# ROS-Robot-Controller.net
KiCad netlist of a schematic drawn in Altium Designer
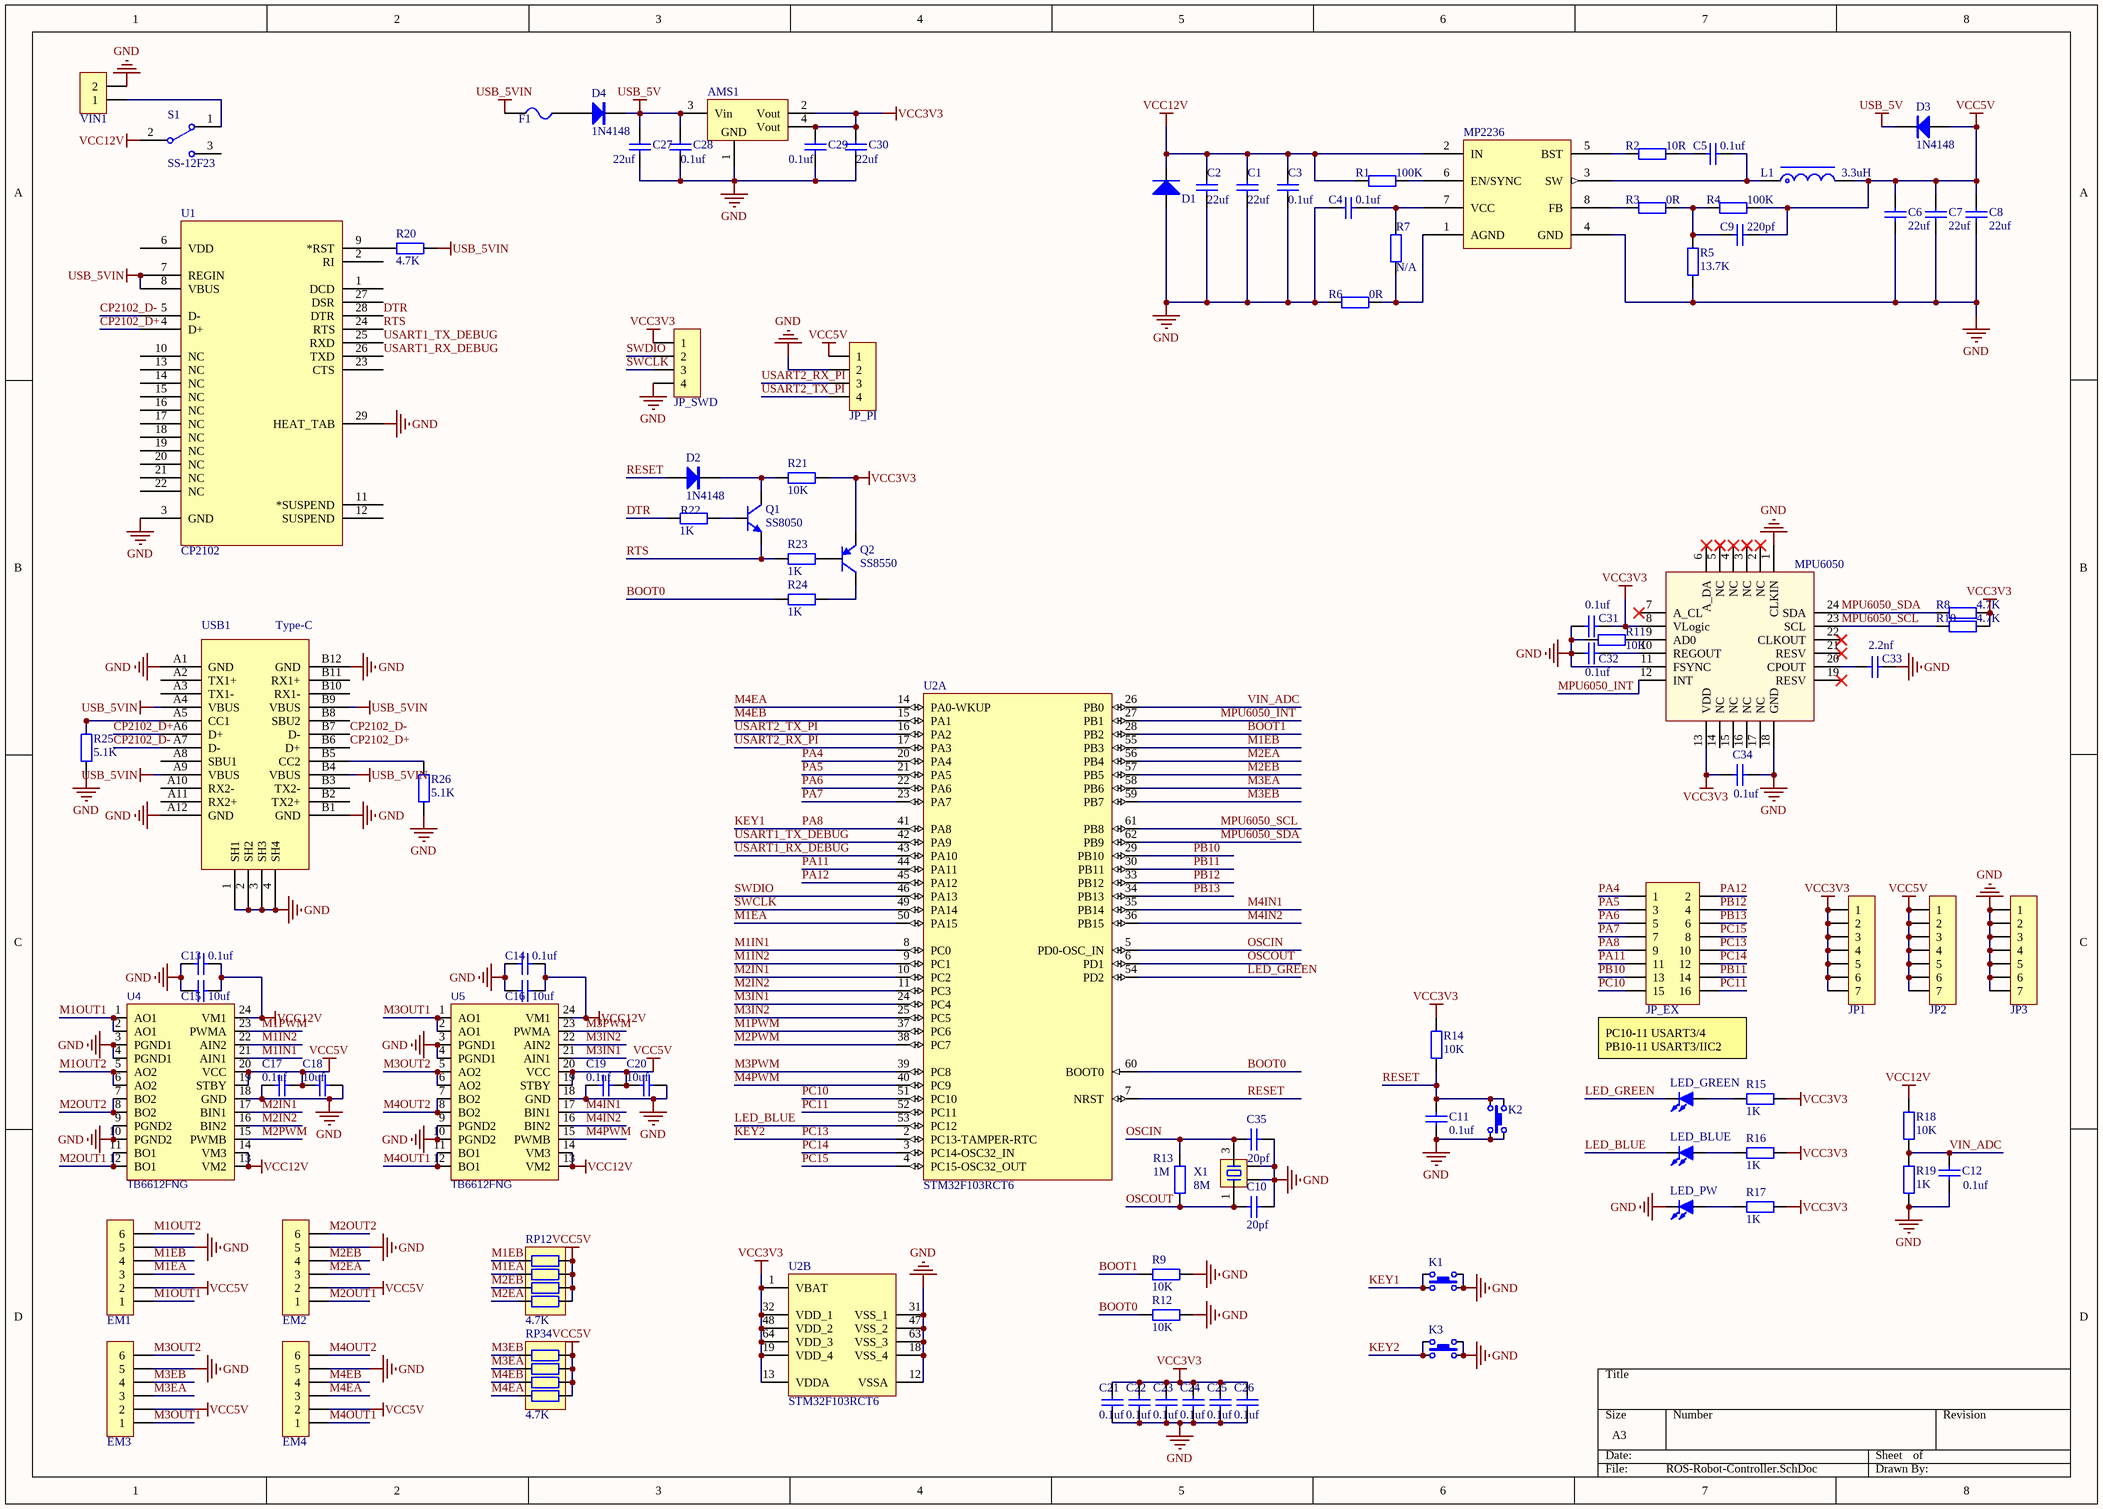
[diagram p0: ROS-Robot-Controller.SchDoc]

(export (version "E")
  (design (tool "Eeschema 10.0.6"))
  (components
    (comp (ref "AMS1")
      (value "AMS1117-3V3")
      (footprint "SOT223_L")
      (description "三端稳压芯片")
      (libsource (lib "1.1 - 电源类芯片") (part "AMS1117"))
    )
    (comp (ref "C1")
      (value "22uf")
      (footprint "C1206_L")
      (description "贴片电容")
      (libsource (lib "0.1 - 电阻-电容-电感-电位器") (part "C"))
    )
    (comp (ref "C2")
      (value "22uf")
      (footprint "C1206_L")
      (description "贴片电容")
      (libsource (lib "0.1 - 电阻-电容-电感-电位器") (part "C"))
    )
    (comp (ref "C3")
      (value "0.1uf")
      (footprint "C0603_L")
      (description "贴片电容")
      (libsource (lib "0.1 - 电阻-电容-电感-电位器") (part "C"))
    )
    (comp (ref "C4")
      (value "0.1uf")
      (footprint "C0603_L")
      (description "贴片电容")
      (libsource (lib "0.1 - 电阻-电容-电感-电位器") (part "C"))
    )
    (comp (ref "C5")
      (value "0.1uf")
      (footprint "C0603_L")
      (description "贴片电容")
      (libsource (lib "0.1 - 电阻-电容-电感-电位器") (part "C"))
    )
    (comp (ref "C6")
      (value "22uf")
      (footprint "C0805_L")
      (description "贴片电容")
      (libsource (lib "0.1 - 电阻-电容-电感-电位器") (part "C"))
    )
    (comp (ref "C7")
      (value "22uf")
      (footprint "C0805_L")
      (description "贴片电容")
      (libsource (lib "0.1 - 电阻-电容-电感-电位器") (part "C"))
    )
    (comp (ref "C8")
      (value "22uf")
      (footprint "C0805_L")
      (description "贴片电容")
      (libsource (lib "0.1 - 电阻-电容-电感-电位器") (part "C"))
    )
    (comp (ref "C9")
      (value "220pf")
      (footprint "C0603_L")
      (description "贴片电容")
      (libsource (lib "0.1 - 电阻-电容-电感-电位器") (part "C"))
    )
    (comp (ref "C10")
      (value "20pf")
      (footprint "C0402_L")
      (description "贴片电容")
      (libsource (lib "0.1 - 电阻-电容-电感-电位器") (part "C"))
    )
    (comp (ref "C11")
      (value "0.1uf")
      (footprint "C0402_L")
      (description "贴片电容")
      (libsource (lib "0.1 - 电阻-电容-电感-电位器") (part "C"))
    )
    (comp (ref "C12")
      (value "0.1uf")
      (footprint "C0603_L")
      (description "贴片电容")
      (libsource (lib "0.1 - 电阻-电容-电感-电位器") (part "C"))
    )
    (comp (ref "C13")
      (value "0.1uf")
      (footprint "C0603_L")
      (description "贴片电容")
      (libsource (lib "0.1 - 电阻-电容-电感-电位器") (part "C"))
    )
    (comp (ref "C14")
      (value "0.1uf")
      (footprint "C0603_L")
      (description "贴片电容")
      (libsource (lib "0.1 - 电阻-电容-电感-电位器") (part "C"))
    )
    (comp (ref "C15")
      (value "10uf")
      (footprint "C0603_L")
      (description "贴片电容")
      (libsource (lib "0.1 - 电阻-电容-电感-电位器") (part "C"))
    )
    (comp (ref "C16")
      (value "10uf")
      (footprint "C0603_L")
      (description "贴片电容")
      (libsource (lib "0.1 - 电阻-电容-电感-电位器") (part "C"))
    )
    (comp (ref "C17")
      (value "0.1uf")
      (footprint "C0402_L")
      (description "贴片电容")
      (libsource (lib "0.1 - 电阻-电容-电感-电位器") (part "C"))
    )
    (comp (ref "C18")
      (value "10uf")
      (footprint "C0402_L")
      (description "贴片电容")
      (libsource (lib "0.1 - 电阻-电容-电感-电位器") (part "C"))
    )
    (comp (ref "C19")
      (value "0.1uf")
      (footprint "C0402_L")
      (description "贴片电容")
      (libsource (lib "0.1 - 电阻-电容-电感-电位器") (part "C"))
    )
    (comp (ref "C20")
      (value "10uf")
      (footprint "C0402_L")
      (description "贴片电容")
      (libsource (lib "0.1 - 电阻-电容-电感-电位器") (part "C"))
    )
    (comp (ref "C21")
      (value "0.1uf")
      (footprint "C0402_L")
      (description "贴片电容")
      (libsource (lib "0.1 - 电阻-电容-电感-电位器") (part "C"))
    )
    (comp (ref "C22")
      (value "0.1uf")
      (footprint "C0402_L")
      (description "贴片电容")
      (libsource (lib "0.1 - 电阻-电容-电感-电位器") (part "C"))
    )
    (comp (ref "C23")
      (value "0.1uf")
      (footprint "C0402_L")
      (description "贴片电容")
      (libsource (lib "0.1 - 电阻-电容-电感-电位器") (part "C"))
    )
    (comp (ref "C24")
      (value "0.1uf")
      (footprint "C0402_L")
      (description "贴片电容")
      (libsource (lib "0.1 - 电阻-电容-电感-电位器") (part "C"))
    )
    (comp (ref "C25")
      (value "0.1uf")
      (footprint "C0402_L")
      (description "贴片电容")
      (libsource (lib "0.1 - 电阻-电容-电感-电位器") (part "C"))
    )
    (comp (ref "C26")
      (value "0.1uf")
      (footprint "C0402_L")
      (description "贴片电容")
      (libsource (lib "0.1 - 电阻-电容-电感-电位器") (part "C"))
    )
    (comp (ref "C27")
      (value "22uf")
      (footprint "C0603_L")
      (description "贴片电容")
      (libsource (lib "0.1 - 电阻-电容-电感-电位器") (part "C"))
    )
    (comp (ref "C28")
      (value "0.1uf")
      (footprint "C0603_L")
      (description "贴片电容")
      (libsource (lib "0.1 - 电阻-电容-电感-电位器") (part "C"))
    )
    (comp (ref "C29")
      (value "0.1uf")
      (footprint "C0603_L")
      (description "贴片电容")
      (libsource (lib "0.1 - 电阻-电容-电感-电位器") (part "C"))
    )
    (comp (ref "C30")
      (value "22uf")
      (footprint "C0603_L")
      (description "贴片电容")
      (libsource (lib "0.1 - 电阻-电容-电感-电位器") (part "C"))
    )
    (comp (ref "C31")
      (value "0.1uf")
      (footprint "C0402_L")
      (description "贴片电容")
      (libsource (lib "0.1 - 电阻-电容-电感-电位器") (part "C"))
    )
    (comp (ref "C32")
      (value "0.1uf")
      (footprint "C0402_L")
      (description "贴片电容")
      (libsource (lib "0.1 - 电阻-电容-电感-电位器") (part "C"))
    )
    (comp (ref "C33")
      (value "2.2nf")
      (footprint "C0402_L")
      (description "贴片电容")
      (libsource (lib "0.1 - 电阻-电容-电感-电位器") (part "C"))
    )
    (comp (ref "C34")
      (value "0.1uf")
      (footprint "C0402_L")
      (description "贴片电容")
      (libsource (lib "0.1 - 电阻-电容-电感-电位器") (part "C"))
    )
    (comp (ref "C35")
      (value "20pf")
      (footprint "C0402_L")
      (description "贴片电容")
      (libsource (lib "0.1 - 电阻-电容-电感-电位器") (part "C"))
    )
    (comp (ref "D1")
      (value "SMAJ12A")
      (footprint "SMA")
      (description "TVS通用")
      (libsource (lib "0.2 - 二极管-TVS-整流桥") (part "TVS"))
    )
    (comp (ref "D2")
      (value "1N4148")
      (footprint "SOD-323")
      (description "开关二极管")
      (libsource (lib "0.2 - 二极管-TVS-整流桥") (part "1N4148"))
    )
    (comp (ref "D3")
      (value "1N4148")
      (footprint "SOD-323")
      (description "开关二极管")
      (libsource (lib "0.2 - 二极管-TVS-整流桥") (part "1N4148"))
    )
    (comp (ref "D4")
      (value "1N4148")
      (footprint "SOD-323")
      (description "开关二极管")
      (libsource (lib "0.2 - 二极管-TVS-整流桥") (part "1N4148"))
    )
    (comp (ref "EM1")
      (value "HDR-1X6")
      (footprint "XH2.54-LI-6P")
      (description "6P接插件")
      (libsource (lib "5.4 - 接插件-脚距2.54 (100mil) ") (part "Header 6"))
    )
    (comp (ref "EM2")
      (value "HDR-1X6")
      (footprint "XH2.54-LI-6P")
      (description "6P接插件")
      (libsource (lib "5.4 - 接插件-脚距2.54 (100mil) ") (part "Header 6"))
    )
    (comp (ref "EM3")
      (value "HDR-1X6")
      (footprint "XH2.54-LI-6P")
      (description "6P接插件")
      (libsource (lib "5.4 - 接插件-脚距2.54 (100mil) ") (part "Header 6"))
    )
    (comp (ref "EM4")
      (value "HDR-1X6")
      (footprint "XH2.54-LI-6P")
      (description "6P接插件")
      (libsource (lib "5.4 - 接插件-脚距2.54 (100mil) ") (part "Header 6"))
    )
    (comp (ref "F1")
      (value "MSMD200-8V 2A")
      (footprint "FU 0603")
      (description "贴片保险丝")
      (libsource (lib "0.5 - 保险丝-晶振-光耦") (part "FU"))
    )
    (comp (ref "JP1")
      (value "HDR-1X7")
      (footprint "HDR2.54-LI-7P")
      (description "7P接插件")
      (libsource (lib "5.4 - 接插件-脚距2.54 (100mil) ") (part "Header 7"))
    )
    (comp (ref "JP2")
      (value "HDR-1X7")
      (footprint "HDR2.54-LI-7P")
      (description "7P接插件")
      (libsource (lib "5.4 - 接插件-脚距2.54 (100mil) ") (part "Header 7"))
    )
    (comp (ref "JP3")
      (value "HDR-1X7")
      (footprint "HDR2.54-LI-7P")
      (description "7P接插件")
      (libsource (lib "5.4 - 接插件-脚距2.54 (100mil) ") (part "Header 7"))
    )
    (comp (ref "JP_EX")
      (value "Header 8X2")
      (footprint "HDR2.54-LI-2x8P")
      (description "8*2P接插件")
      (libsource (lib "5.4 - 接插件-脚距2.54 (100mil) ") (part "Header 8X2"))
    )
    (comp (ref "JP_PI")
      (value "HDR-1X4")
      (footprint "HDR2.54-LI-4P")
      (description "4P接插件")
      (libsource (lib "5.4 - 接插件-脚距2.54 (100mil) ") (part "Header 4"))
    )
    (comp (ref "JP_SWD")
      (value "HDR-1X4")
      (footprint "XH2.54-WI-4P")
      (description "4P接插件")
      (libsource (lib "5.4 - 接插件-脚距2.54 (100mil) ") (part "Header 4"))
    )
    (comp (ref "K1")
      (value "TACT 4P")
      (footprint "SW-SMD_4P-L4.2-W3.3-P2.15-LS5.1")
      (description "Button")
      (libsource (lib "KitSprout") (part "ButtonTACT"))
    )
    (comp (ref "K2")
      (value "TACT 4P")
      (footprint "SW-SMD_4P-L4.2-W3.3-P2.15-LS5.1")
      (description "Button")
      (libsource (lib "KitSprout") (part "ButtonTACT"))
    )
    (comp (ref "K3")
      (value "TACT 4P")
      (footprint "SW-SMD_4P-L4.2-W3.3-P2.15-LS5.1")
      (description "Button")
      (libsource (lib "KitSprout") (part "ButtonTACT"))
    )
    (comp (ref "L1")
      (value "3.3uH")
      (footprint "L-SMD-0630")
      (description "一体成型电感")
      (libsource (lib "0.1 - 电阻-电容-电感-电位器") (part "L-Molding Choke"))
    )
    (comp (ref "LED_BLUE")
      (value "红色")
      (footprint "LED_0402_RED")
      (description "贴片LED")
      (libsource (lib "0.3 - LED发光二极管") (part "LED-SMD"))
    )
    (comp (ref "LED_GREEN")
      (value "红色")
      (footprint "LED_0402_RED")
      (description "贴片LED")
      (libsource (lib "0.3 - LED发光二极管") (part "LED-SMD"))
    )
    (comp (ref "LED_PW")
      (value "红色")
      (footprint "LED_0402_RED")
      (description "贴片LED")
      (libsource (lib "0.3 - LED发光二极管") (part "LED-SMD"))
    )
    (comp (ref "MP2236")
      (value "MP2236")
      (footprint "TSOT23-8_MP2225_MNP")
      (libsource (lib "MP2225") (part "MP2225修改版"))
    )
    (comp (ref "Q1")
      (value "SS8050")
      (footprint "SOT23-3N")
      (description "高频放大-NPN型")
      (libsource (lib "0.4 - 三极管-场效应管-可控硅") (part "8050-SMD"))
    )
    (comp (ref "Q2")
      (value "SS8550")
      (footprint "SOT23-3N")
      (description "高频放大-PNP型")
      (libsource (lib "0.4 - 三极管-场效应管-可控硅") (part "8550-SMD"))
    )
    (comp (ref "R1")
      (value "100K")
      (footprint "R0603_L")
      (description "贴片电阻")
      (libsource (lib "0.1 - 电阻-电容-电感-电位器") (part "R"))
    )
    (comp (ref "R2")
      (value "10R")
      (footprint "R0603_L")
      (description "贴片电阻")
      (libsource (lib "0.1 - 电阻-电容-电感-电位器") (part "R"))
    )
    (comp (ref "R3")
      (value "0R")
      (footprint "R0603_L")
      (description "贴片电阻")
      (libsource (lib "0.1 - 电阻-电容-电感-电位器") (part "R"))
    )
    (comp (ref "R4")
      (value "100K")
      (footprint "R0603_L")
      (description "贴片电阻")
      (libsource (lib "0.1 - 电阻-电容-电感-电位器") (part "R"))
    )
    (comp (ref "R5")
      (value "13.7K")
      (footprint "R0603_L")
      (description "贴片电阻")
      (libsource (lib "0.1 - 电阻-电容-电感-电位器") (part "R"))
    )
    (comp (ref "R6")
      (value "0R")
      (footprint "R0603_L")
      (description "贴片电阻")
      (libsource (lib "0.1 - 电阻-电容-电感-电位器") (part "R"))
    )
    (comp (ref "R7")
      (value "N/A")
      (footprint "R0603_L")
      (description "贴片电阻")
      (libsource (lib "0.1 - 电阻-电容-电感-电位器") (part "R"))
    )
    (comp (ref "R8")
      (value "4.7K")
      (footprint "R0402_L")
      (description "贴片电阻")
      (libsource (lib "0.1 - 电阻-电容-电感-电位器") (part "R"))
    )
    (comp (ref "R9")
      (value "10K")
      (footprint "R0402_L")
      (description "贴片电阻")
      (libsource (lib "0.1 - 电阻-电容-电感-电位器") (part "R"))
    )
    (comp (ref "R10")
      (value "4.7K")
      (footprint "R0402_L")
      (description "贴片电阻")
      (libsource (lib "0.1 - 电阻-电容-电感-电位器") (part "R"))
    )
    (comp (ref "R11")
      (value "10K")
      (footprint "R0402_L")
      (description "贴片电阻")
      (libsource (lib "0.1 - 电阻-电容-电感-电位器") (part "R"))
    )
    (comp (ref "R12")
      (value "10K")
      (footprint "R0402_L")
      (description "贴片电阻")
      (libsource (lib "0.1 - 电阻-电容-电感-电位器") (part "R"))
    )
    (comp (ref "R13")
      (value "1M")
      (footprint "R0402_L")
      (description "贴片电阻")
      (libsource (lib "0.1 - 电阻-电容-电感-电位器") (part "R"))
    )
    (comp (ref "R14")
      (value "10K")
      (footprint "R0402_L")
      (description "贴片电阻")
      (libsource (lib "0.1 - 电阻-电容-电感-电位器") (part "R"))
    )
    (comp (ref "R15")
      (value "1K")
      (footprint "R0402_L")
      (description "贴片电阻")
      (libsource (lib "0.1 - 电阻-电容-电感-电位器") (part "R"))
    )
    (comp (ref "R16")
      (value "1K")
      (footprint "R0402_L")
      (description "贴片电阻")
      (libsource (lib "0.1 - 电阻-电容-电感-电位器") (part "R"))
    )
    (comp (ref "R17")
      (value "1K")
      (footprint "R0402_L")
      (description "贴片电阻")
      (libsource (lib "0.1 - 电阻-电容-电感-电位器") (part "R"))
    )
    (comp (ref "R18")
      (value "10K")
      (footprint "R0603_L")
      (description "贴片电阻")
      (libsource (lib "0.1 - 电阻-电容-电感-电位器") (part "R"))
    )
    (comp (ref "R19")
      (value "1K")
      (footprint "R0603_L")
      (description "贴片电阻")
      (libsource (lib "0.1 - 电阻-电容-电感-电位器") (part "R"))
    )
    (comp (ref "R20")
      (value "4.7K")
      (footprint "R0402_L")
      (description "贴片电阻")
      (libsource (lib "0.1 - 电阻-电容-电感-电位器") (part "R"))
    )
    (comp (ref "R21")
      (value "10K")
      (footprint "R0402_L")
      (description "贴片电阻")
      (libsource (lib "0.1 - 电阻-电容-电感-电位器") (part "R"))
    )
    (comp (ref "R22")
      (value "1K")
      (footprint "R0402_L")
      (description "贴片电阻")
      (libsource (lib "0.1 - 电阻-电容-电感-电位器") (part "R"))
    )
    (comp (ref "R23")
      (value "1K")
      (footprint "R0402_L")
      (description "贴片电阻")
      (libsource (lib "0.1 - 电阻-电容-电感-电位器") (part "R"))
    )
    (comp (ref "R24")
      (value "1K")
      (footprint "R0402_L")
      (description "贴片电阻")
      (libsource (lib "0.1 - 电阻-电容-电感-电位器") (part "R"))
    )
    (comp (ref "R25")
      (value "5.1K")
      (footprint "R0402_L")
      (description "贴片电阻")
      (libsource (lib "0.1 - 电阻-电容-电感-电位器") (part "R"))
    )
    (comp (ref "R26")
      (value "5.1K")
      (footprint "R0402_L")
      (description "贴片电阻")
      (libsource (lib "0.1 - 电阻-电容-电感-电位器") (part "R"))
    )
    (comp (ref "RP12")
      (value "4.7K")
      (footprint "RCA-8P4R-0402")
      (description "贴片4P排阻")
      (libsource (lib "0.1 - 电阻-电容-电感-电位器") (part "R-8P4R"))
    )
    (comp (ref "RP34")
      (value "4.7K")
      (footprint "RCA-8P4R-0402")
      (description "贴片4P排阻")
      (libsource (lib "0.1 - 电阻-电容-电感-电位器") (part "R-8P4R"))
    )
    (comp (ref "S1")
      (value "SS-12F23")
      (footprint "SS-12D10")
      (description "1路波动开关")
      (libsource (lib "0.7 - 常用按键-开关-蜂鸣器-电池-测试点") (part "SSW-1P"))
    )
    (comp (ref "U1")
      (value "CP2102")
      (footprint "QFN-28")
      (description "USB转TTL")
      (libsource (lib "mLib") (part "CP2102"))
    )
    (comp (ref "U2")
      (value "STM32F103RCT6")
      (footprint "LQFP64_N")
      (libsource (lib "2.4 - STM32 F1系列单片机") (part "STM32F103RCT6"))
    )
    (comp (ref "U3")
      (value "MPU6050")
      (footprint "QFN-24")
      (description "六轴传感器")
      (libsource (lib "mLib") (part "MPU6050"))
    )
    (comp (ref "U4")
      (value "TB6612FNG")
      (footprint "SSOP24_M")
      (description "电机驱动")
      (libsource (lib "1.0 - 常见芯片") (part "TB6612FNG"))
    )
    (comp (ref "U5")
      (value "TB6612FNG")
      (footprint "SSOP24_M")
      (description "电机驱动")
      (libsource (lib "1.0 - 常见芯片") (part "TB6612FNG"))
    )
    (comp (ref "USB1")
      (value "Type-C")
      (footprint "Type-C-TOP")
      (libsource (lib "MyPcbLib") (part "USB-Type-C-TOP"))
    )
    (comp (ref "VIN1")
      (value "HDR-1X2")
      (footprint "KF301-5.0-2P")
      (description "2P接插件")
      (libsource (lib "6.0 - 接插件-脚距5.0") (part "Header 2"))
    )
    (comp (ref "X1")
      (value "8M")
      (footprint "OSC 3225-4P")
      (description "4脚无源晶振")
      (libsource (lib "0.5 - 保险丝-晶振-光耦") (part "XTAL-4P"))
    )
  )
  (nets
    (net (code "1") (name "/BOOT0") (class "Default")
      (node (ref "R12") (pin "1") (pinfunction "1_1") (pintype "passive"))
      (node (ref "R24") (pin "2") (pinfunction "2_2") (pintype "passive"))
      (node (ref "U2") (pin "60") (pinfunction "BOOT0_60") (pintype "input"))
    )
    (net (code "2") (name "/BOOT1") (class "Default")
      (node (ref "R9") (pin "1") (pinfunction "1_1") (pintype "passive"))
      (node (ref "U2") (pin "28") (pinfunction "PB2_28") (pintype "bidirectional"))
    )
    (net (code "3") (name "/CP2102_D+") (class "Default")
      (node (ref "U1") (pin "4") (pinfunction "D+_4") (pintype "passive"))
      (node (ref "USB1") (pin "A6") (pinfunction "D+_A6") (pintype "passive"))
      (node (ref "USB1") (pin "B6") (pinfunction "D+_B6") (pintype "passive"))
    )
    (net (code "4") (name "/CP2102_D-") (class "Default")
      (node (ref "U1") (pin "5") (pinfunction "D-_5") (pintype "passive"))
      (node (ref "USB1") (pin "A7") (pinfunction "D-_A7") (pintype "passive"))
      (node (ref "USB1") (pin "B7") (pinfunction "D-_B7") (pintype "passive"))
    )
    (net (code "5") (name "/DTR") (class "Default")
      (node (ref "R22") (pin "1") (pinfunction "1_1") (pintype "passive"))
      (node (ref "U1") (pin "28") (pinfunction "DTR_28") (pintype "passive"))
    )
    (net (code "6") (name "/KEY1") (class "Default")
      (node (ref "JP_EX") (pin "9") (pinfunction "9_9") (pintype "passive"))
      (node (ref "K1") (pin "1") (pinfunction "1_1") (pintype "passive"))
      (node (ref "K1") (pin "3") (pinfunction "3_3") (pintype "passive"))
      (node (ref "U2") (pin "41") (pinfunction "PA8_41") (pintype "bidirectional"))
    )
    (net (code "7") (name "/KEY2") (class "Default")
      (node (ref "JP_EX") (pin "10") (pinfunction "10_10") (pintype "passive"))
      (node (ref "K3") (pin "1") (pinfunction "1_1") (pintype "passive"))
      (node (ref "K3") (pin "3") (pinfunction "3_3") (pintype "passive"))
      (node (ref "U2") (pin "2") (pinfunction "PC13-TAMPER-RTC_2") (pintype "bidirectional"))
    )
    (net (code "8") (name "/LED_BLUE") (class "Default")
      (node (ref "LED_BLUE") (pin "2") (pinfunction "K_2") (pintype "passive"))
      (node (ref "U2") (pin "53") (pinfunction "PC12_53") (pintype "bidirectional"))
    )
    (net (code "9") (name "/LED_GREEN") (class "Default")
      (node (ref "LED_GREEN") (pin "2") (pinfunction "K_2") (pintype "passive"))
      (node (ref "U2") (pin "54") (pinfunction "PD2_54") (pintype "bidirectional"))
    )
    (net (code "10") (name "/M1EA") (class "Default")
      (node (ref "EM1") (pin "3") (pinfunction "3_3") (pintype "passive"))
      (node (ref "RP12") (pin "2") (pinfunction "2_2") (pintype "passive"))
      (node (ref "U2") (pin "50") (pinfunction "PA15_50") (pintype "bidirectional"))
    )
    (net (code "11") (name "/M1EB") (class "Default")
      (node (ref "EM1") (pin "4") (pinfunction "4_4") (pintype "passive"))
      (node (ref "RP12") (pin "1") (pinfunction "1_1") (pintype "passive"))
      (node (ref "U2") (pin "55") (pinfunction "PB3_55") (pintype "bidirectional"))
    )
    (net (code "12") (name "/M1IN1") (class "Default")
      (node (ref "U2") (pin "8") (pinfunction "PC0_8") (pintype "bidirectional"))
      (node (ref "U4") (pin "21") (pinfunction "AIN1_21") (pintype "passive"))
    )
    (net (code "13") (name "/M1IN2") (class "Default")
      (node (ref "U2") (pin "9") (pinfunction "PC1_9") (pintype "bidirectional"))
      (node (ref "U4") (pin "22") (pinfunction "AIN2_22") (pintype "passive"))
    )
    (net (code "14") (name "/M1OUT1") (class "Default")
      (node (ref "EM1") (pin "1") (pinfunction "1_1") (pintype "passive"))
      (node (ref "U4") (pin "1") (pinfunction "AO1_1") (pintype "passive"))
      (node (ref "U4") (pin "2") (pinfunction "AO1_2") (pintype "passive"))
    )
    (net (code "15") (name "/M1OUT2") (class "Default")
      (node (ref "EM1") (pin "6") (pinfunction "6_6") (pintype "passive"))
      (node (ref "U4") (pin "5") (pinfunction "AO2_5") (pintype "passive"))
      (node (ref "U4") (pin "6") (pinfunction "AO2_6") (pintype "passive"))
    )
    (net (code "16") (name "/M1PWM") (class "Default")
      (node (ref "U2") (pin "37") (pinfunction "PC6_37") (pintype "bidirectional"))
      (node (ref "U4") (pin "23") (pinfunction "PWMA_23") (pintype "passive"))
    )
    (net (code "17") (name "/M2EA") (class "Default")
      (node (ref "EM2") (pin "3") (pinfunction "3_3") (pintype "passive"))
      (node (ref "RP12") (pin "4") (pinfunction "4_4") (pintype "passive"))
      (node (ref "U2") (pin "56") (pinfunction "PB4_56") (pintype "bidirectional"))
    )
    (net (code "18") (name "/M2EB") (class "Default")
      (node (ref "EM2") (pin "4") (pinfunction "4_4") (pintype "passive"))
      (node (ref "RP12") (pin "3") (pinfunction "3_3") (pintype "passive"))
      (node (ref "U2") (pin "57") (pinfunction "PB5_57") (pintype "bidirectional"))
    )
    (net (code "19") (name "/M2IN1") (class "Default")
      (node (ref "U2") (pin "10") (pinfunction "PC2_10") (pintype "bidirectional"))
      (node (ref "U4") (pin "17") (pinfunction "BIN1_17") (pintype "passive"))
    )
    (net (code "20") (name "/M2IN2") (class "Default")
      (node (ref "U2") (pin "11") (pinfunction "PC3_11") (pintype "bidirectional"))
      (node (ref "U4") (pin "16") (pinfunction "BIN2_16") (pintype "passive"))
    )
    (net (code "21") (name "/M2OUT1") (class "Default")
      (node (ref "EM2") (pin "1") (pinfunction "1_1") (pintype "passive"))
      (node (ref "U4") (pin "11") (pinfunction "BO1_11") (pintype "passive"))
      (node (ref "U4") (pin "12") (pinfunction "BO1_12") (pintype "passive"))
    )
    (net (code "22") (name "/M2OUT2") (class "Default")
      (node (ref "EM2") (pin "6") (pinfunction "6_6") (pintype "passive"))
      (node (ref "U4") (pin "7") (pinfunction "BO2_7") (pintype "passive"))
      (node (ref "U4") (pin "8") (pinfunction "BO2_8") (pintype "passive"))
    )
    (net (code "23") (name "/M2PWM") (class "Default")
      (node (ref "U2") (pin "38") (pinfunction "PC7_38") (pintype "bidirectional"))
      (node (ref "U4") (pin "15") (pinfunction "PWMB_15") (pintype "passive"))
    )
    (net (code "24") (name "/M3EA") (class "Default")
      (node (ref "EM3") (pin "3") (pinfunction "3_3") (pintype "passive"))
      (node (ref "RP34") (pin "2") (pinfunction "2_2") (pintype "passive"))
      (node (ref "U2") (pin "58") (pinfunction "PB6_58") (pintype "bidirectional"))
    )
    (net (code "25") (name "/M3EB") (class "Default")
      (node (ref "EM3") (pin "4") (pinfunction "4_4") (pintype "passive"))
      (node (ref "RP34") (pin "1") (pinfunction "1_1") (pintype "passive"))
      (node (ref "U2") (pin "59") (pinfunction "PB7_59") (pintype "bidirectional"))
    )
    (net (code "26") (name "/M3IN1") (class "Default")
      (node (ref "U2") (pin "24") (pinfunction "PC4_24") (pintype "bidirectional"))
      (node (ref "U5") (pin "21") (pinfunction "AIN1_21") (pintype "passive"))
    )
    (net (code "27") (name "/M3IN2") (class "Default")
      (node (ref "U2") (pin "25") (pinfunction "PC5_25") (pintype "bidirectional"))
      (node (ref "U5") (pin "22") (pinfunction "AIN2_22") (pintype "passive"))
    )
    (net (code "28") (name "/M3OUT1") (class "Default")
      (node (ref "EM3") (pin "1") (pinfunction "1_1") (pintype "passive"))
      (node (ref "U5") (pin "1") (pinfunction "AO1_1") (pintype "passive"))
      (node (ref "U5") (pin "2") (pinfunction "AO1_2") (pintype "passive"))
    )
    (net (code "29") (name "/M3OUT2") (class "Default")
      (node (ref "EM3") (pin "6") (pinfunction "6_6") (pintype "passive"))
      (node (ref "U5") (pin "5") (pinfunction "AO2_5") (pintype "passive"))
      (node (ref "U5") (pin "6") (pinfunction "AO2_6") (pintype "passive"))
    )
    (net (code "30") (name "/M3PWM") (class "Default")
      (node (ref "U2") (pin "39") (pinfunction "PC8_39") (pintype "bidirectional"))
      (node (ref "U5") (pin "23") (pinfunction "PWMA_23") (pintype "passive"))
    )
    (net (code "31") (name "/M4EA") (class "Default")
      (node (ref "EM4") (pin "3") (pinfunction "3_3") (pintype "passive"))
      (node (ref "RP34") (pin "4") (pinfunction "4_4") (pintype "passive"))
      (node (ref "U2") (pin "14") (pinfunction "PA0-WKUP_14") (pintype "bidirectional"))
    )
    (net (code "32") (name "/M4EB") (class "Default")
      (node (ref "EM4") (pin "4") (pinfunction "4_4") (pintype "passive"))
      (node (ref "RP34") (pin "3") (pinfunction "3_3") (pintype "passive"))
      (node (ref "U2") (pin "15") (pinfunction "PA1_15") (pintype "bidirectional"))
    )
    (net (code "33") (name "/M4IN1") (class "Default")
      (node (ref "U2") (pin "35") (pinfunction "PB14_35") (pintype "bidirectional"))
      (node (ref "U5") (pin "17") (pinfunction "BIN1_17") (pintype "passive"))
    )
    (net (code "34") (name "/M4IN2") (class "Default")
      (node (ref "U2") (pin "36") (pinfunction "PB15_36") (pintype "bidirectional"))
      (node (ref "U5") (pin "16") (pinfunction "BIN2_16") (pintype "passive"))
    )
    (net (code "35") (name "/M4OUT1") (class "Default")
      (node (ref "EM4") (pin "1") (pinfunction "1_1") (pintype "passive"))
      (node (ref "U5") (pin "11") (pinfunction "BO1_11") (pintype "passive"))
      (node (ref "U5") (pin "12") (pinfunction "BO1_12") (pintype "passive"))
    )
    (net (code "36") (name "/M4OUT2") (class "Default")
      (node (ref "EM4") (pin "6") (pinfunction "6_6") (pintype "passive"))
      (node (ref "U5") (pin "7") (pinfunction "BO2_7") (pintype "passive"))
      (node (ref "U5") (pin "8") (pinfunction "BO2_8") (pintype "passive"))
    )
    (net (code "37") (name "/M4PWM") (class "Default")
      (node (ref "U2") (pin "40") (pinfunction "PC9_40") (pintype "bidirectional"))
      (node (ref "U5") (pin "15") (pinfunction "PWMB_15") (pintype "passive"))
    )
    (net (code "38") (name "/MPU6050_INT") (class "Default")
      (node (ref "U2") (pin "27") (pinfunction "PB1_27") (pintype "bidirectional"))
      (node (ref "U3") (pin "12") (pinfunction "INT_12") (pintype "passive"))
    )
    (net (code "39") (name "/MPU6050_SCL") (class "Default")
      (node (ref "R10") (pin "1") (pinfunction "1_1") (pintype "passive"))
      (node (ref "U2") (pin "61") (pinfunction "PB8_61") (pintype "bidirectional"))
      (node (ref "U3") (pin "23") (pinfunction "SCL_23") (pintype "passive"))
    )
    (net (code "40") (name "/MPU6050_SDA") (class "Default")
      (node (ref "R8") (pin "1") (pinfunction "1_1") (pintype "passive"))
      (node (ref "U2") (pin "62") (pinfunction "PB9_62") (pintype "bidirectional"))
      (node (ref "U3") (pin "24") (pinfunction "SDA_24") (pintype "passive"))
    )
    (net (code "41") (name "/OSCIN") (class "Default")
      (node (ref "C35") (pin "1") (pinfunction "1_1") (pintype "passive"))
      (node (ref "R13") (pin "2") (pinfunction "2_2") (pintype "passive"))
      (node (ref "U2") (pin "5") (pinfunction "PD0-OSC_IN_5") (pintype "bidirectional"))
      (node (ref "X1") (pin "3") (pinfunction "3_3") (pintype "passive"))
    )
    (net (code "42") (name "/OSCOUT") (class "Default")
      (node (ref "C10") (pin "1") (pinfunction "1_1") (pintype "passive"))
      (node (ref "R13") (pin "1") (pinfunction "1_1") (pintype "passive"))
      (node (ref "U2") (pin "6") (pinfunction "PD1_6") (pintype "bidirectional"))
      (node (ref "X1") (pin "1") (pinfunction "1_1") (pintype "passive"))
    )
    (net (code "43") (name "/PA4") (class "Default")
      (node (ref "JP_EX") (pin "1") (pinfunction "1_1") (pintype "passive"))
      (node (ref "U2") (pin "20") (pinfunction "PA4_20") (pintype "bidirectional"))
    )
    (net (code "44") (name "/PA5") (class "Default")
      (node (ref "JP_EX") (pin "3") (pinfunction "3_3") (pintype "passive"))
      (node (ref "U2") (pin "21") (pinfunction "PA5_21") (pintype "bidirectional"))
    )
    (net (code "45") (name "/PA6") (class "Default")
      (node (ref "JP_EX") (pin "5") (pinfunction "5_5") (pintype "passive"))
      (node (ref "U2") (pin "22") (pinfunction "PA6_22") (pintype "bidirectional"))
    )
    (net (code "46") (name "/PA7") (class "Default")
      (node (ref "JP_EX") (pin "7") (pinfunction "7_7") (pintype "passive"))
      (node (ref "U2") (pin "23") (pinfunction "PA7_23") (pintype "bidirectional"))
    )
    (net (code "47") (name "/PA11") (class "Default")
      (node (ref "JP_EX") (pin "11") (pinfunction "11_11") (pintype "passive"))
      (node (ref "U2") (pin "44") (pinfunction "PA11_44") (pintype "bidirectional"))
    )
    (net (code "48") (name "/PA12") (class "Default")
      (node (ref "JP_EX") (pin "2") (pinfunction "2_2") (pintype "passive"))
      (node (ref "U2") (pin "45") (pinfunction "PA12_45") (pintype "bidirectional"))
    )
    (net (code "49") (name "/PB10") (class "Default")
      (node (ref "JP_EX") (pin "13") (pinfunction "13_13") (pintype "passive"))
      (node (ref "U2") (pin "29") (pinfunction "PB10_29") (pintype "bidirectional"))
    )
    (net (code "50") (name "/PB11") (class "Default")
      (node (ref "JP_EX") (pin "14") (pinfunction "14_14") (pintype "passive"))
      (node (ref "U2") (pin "30") (pinfunction "PB11_30") (pintype "bidirectional"))
    )
    (net (code "51") (name "/PB12") (class "Default")
      (node (ref "JP_EX") (pin "4") (pinfunction "4_4") (pintype "passive"))
      (node (ref "U2") (pin "33") (pinfunction "PB12_33") (pintype "bidirectional"))
    )
    (net (code "52") (name "/PB13") (class "Default")
      (node (ref "JP_EX") (pin "6") (pinfunction "6_6") (pintype "passive"))
      (node (ref "U2") (pin "34") (pinfunction "PB13_34") (pintype "bidirectional"))
    )
    (net (code "53") (name "/PC10") (class "Default")
      (node (ref "JP_EX") (pin "15") (pinfunction "15_15") (pintype "passive"))
      (node (ref "U2") (pin "51") (pinfunction "PC10_51") (pintype "bidirectional"))
    )
    (net (code "54") (name "/PC11") (class "Default")
      (node (ref "JP_EX") (pin "16") (pinfunction "16_16") (pintype "passive"))
      (node (ref "U2") (pin "52") (pinfunction "PC11_52") (pintype "bidirectional"))
    )
    (net (code "55") (name "/PC14") (class "Default")
      (node (ref "JP_EX") (pin "12") (pinfunction "12_12") (pintype "passive"))
      (node (ref "U2") (pin "3") (pinfunction "PC14-OSC32_IN_3") (pintype "bidirectional"))
    )
    (net (code "56") (name "/PC15") (class "Default")
      (node (ref "JP_EX") (pin "8") (pinfunction "8_8") (pintype "passive"))
      (node (ref "U2") (pin "4") (pinfunction "PC15-OSC32_OUT_4") (pintype "bidirectional"))
    )
    (net (code "57") (name "/RESET") (class "Default")
      (node (ref "C11") (pin "2") (pinfunction "2_2") (pintype "passive"))
      (node (ref "D2") (pin "1") (pinfunction "A_1") (pintype "passive"))
      (node (ref "K2") (pin "1") (pinfunction "1_1") (pintype "passive"))
      (node (ref "K2") (pin "3") (pinfunction "3_3") (pintype "passive"))
      (node (ref "R14") (pin "1") (pinfunction "1_1") (pintype "passive"))
      (node (ref "U2") (pin "7") (pinfunction "NRST_7") (pintype "bidirectional"))
    )
    (net (code "58") (name "/RTS") (class "Default")
      (node (ref "Q1") (pin "2") (pinfunction "E_2") (pintype "passive"))
      (node (ref "R23") (pin "1") (pinfunction "1_1") (pintype "passive"))
      (node (ref "U1") (pin "24") (pinfunction "RTS_24") (pintype "passive"))
    )
    (net (code "59") (name "/SWCLK") (class "Default")
      (node (ref "JP_SWD") (pin "3") (pinfunction "3_3") (pintype "passive"))
      (node (ref "U2") (pin "49") (pinfunction "PA14_49") (pintype "bidirectional"))
    )
    (net (code "60") (name "/SWDIO") (class "Default")
      (node (ref "JP_SWD") (pin "2") (pinfunction "2_2") (pintype "passive"))
      (node (ref "U2") (pin "46") (pinfunction "PA13_46") (pintype "bidirectional"))
    )
    (net (code "61") (name "/USART1_RX_DEBUG") (class "Default")
      (node (ref "U1") (pin "26") (pinfunction "TXD_26") (pintype "passive"))
      (node (ref "U2") (pin "43") (pinfunction "PA10_43") (pintype "bidirectional"))
    )
    (net (code "62") (name "/USART1_TX_DEBUG") (class "Default")
      (node (ref "U1") (pin "25") (pinfunction "RXD_25") (pintype "passive"))
      (node (ref "U2") (pin "42") (pinfunction "PA9_42") (pintype "bidirectional"))
    )
    (net (code "63") (name "/USART2_RX_PI") (class "Default")
      (node (ref "JP_PI") (pin "3") (pinfunction "3_3") (pintype "passive"))
      (node (ref "U2") (pin "17") (pinfunction "PA3_17") (pintype "bidirectional"))
    )
    (net (code "64") (name "/USART2_TX_PI") (class "Default")
      (node (ref "JP_PI") (pin "4") (pinfunction "4_4") (pintype "passive"))
      (node (ref "U2") (pin "16") (pinfunction "PA2_16") (pintype "bidirectional"))
    )
    (net (code "65") (name "/VIN_ADC") (class "Default")
      (node (ref "C12") (pin "2") (pinfunction "2_2") (pintype "passive"))
      (node (ref "R18") (pin "1") (pinfunction "1_1") (pintype "passive"))
      (node (ref "R19") (pin "2") (pinfunction "2_2") (pintype "passive"))
      (node (ref "U2") (pin "26") (pinfunction "PB0_26") (pintype "bidirectional"))
    )
    (net (code "66") (name "GND") (class "Default")
      (node (ref "AMS1") (pin "1") (pinfunction "GND_1") (pintype "passive"))
      (node (ref "C1") (pin "1") (pinfunction "1_1") (pintype "passive"))
      (node (ref "C10") (pin "2") (pinfunction "2_2") (pintype "passive"))
      (node (ref "C11") (pin "1") (pinfunction "1_1") (pintype "passive"))
      (node (ref "C12") (pin "1") (pinfunction "1_1") (pintype "passive"))
      (node (ref "C13") (pin "1") (pinfunction "1_1") (pintype "passive"))
      (node (ref "C14") (pin "1") (pinfunction "1_1") (pintype "passive"))
      (node (ref "C15") (pin "1") (pinfunction "1_1") (pintype "passive"))
      (node (ref "C16") (pin "1") (pinfunction "1_1") (pintype "passive"))
      (node (ref "C17") (pin "2") (pinfunction "2_2") (pintype "passive"))
      (node (ref "C18") (pin "1") (pinfunction "1_1") (pintype "passive"))
      (node (ref "C19") (pin "2") (pinfunction "2_2") (pintype "passive"))
      (node (ref "C2") (pin "1") (pinfunction "1_1") (pintype "passive"))
      (node (ref "C20") (pin "1") (pinfunction "1_1") (pintype "passive"))
      (node (ref "C21") (pin "1") (pinfunction "1_1") (pintype "passive"))
      (node (ref "C22") (pin "1") (pinfunction "1_1") (pintype "passive"))
      (node (ref "C23") (pin "1") (pinfunction "1_1") (pintype "passive"))
      (node (ref "C24") (pin "1") (pinfunction "1_1") (pintype "passive"))
      (node (ref "C25") (pin "1") (pinfunction "1_1") (pintype "passive"))
      (node (ref "C26") (pin "1") (pinfunction "1_1") (pintype "passive"))
      (node (ref "C27") (pin "1") (pinfunction "1_1") (pintype "passive"))
      (node (ref "C28") (pin "1") (pinfunction "1_1") (pintype "passive"))
      (node (ref "C29") (pin "1") (pinfunction "1_1") (pintype "passive"))
      (node (ref "C3") (pin "1") (pinfunction "1_1") (pintype "passive"))
      (node (ref "C30") (pin "1") (pinfunction "1_1") (pintype "passive"))
      (node (ref "C31") (pin "1") (pinfunction "1_1") (pintype "passive"))
      (node (ref "C32") (pin "1") (pinfunction "1_1") (pintype "passive"))
      (node (ref "C33") (pin "2") (pinfunction "2_2") (pintype "passive"))
      (node (ref "C34") (pin "2") (pinfunction "2_2") (pintype "passive"))
      (node (ref "C35") (pin "2") (pinfunction "2_2") (pintype "passive"))
      (node (ref "C4") (pin "2") (pinfunction "2_2") (pintype "passive"))
      (node (ref "C6") (pin "1") (pinfunction "1_1") (pintype "passive"))
      (node (ref "C7") (pin "1") (pinfunction "1_1") (pintype "passive"))
      (node (ref "C8") (pin "1") (pinfunction "1_1") (pintype "passive"))
      (node (ref "D1") (pin "1") (pinfunction "A_1") (pintype "passive"))
      (node (ref "EM1") (pin "5") (pinfunction "5_5") (pintype "passive"))
      (node (ref "EM2") (pin "5") (pinfunction "5_5") (pintype "passive"))
      (node (ref "EM3") (pin "5") (pinfunction "5_5") (pintype "passive"))
      (node (ref "EM4") (pin "5") (pinfunction "5_5") (pintype "passive"))
      (node (ref "JP3") (pin "1") (pinfunction "1_1") (pintype "passive"))
      (node (ref "JP3") (pin "2") (pinfunction "2_2") (pintype "passive"))
      (node (ref "JP3") (pin "3") (pinfunction "3_3") (pintype "passive"))
      (node (ref "JP3") (pin "4") (pinfunction "4_4") (pintype "passive"))
      (node (ref "JP3") (pin "5") (pinfunction "5_5") (pintype "passive"))
      (node (ref "JP3") (pin "6") (pinfunction "6_6") (pintype "passive"))
      (node (ref "JP3") (pin "7") (pinfunction "7_7") (pintype "passive"))
      (node (ref "JP_PI") (pin "2") (pinfunction "2_2") (pintype "passive"))
      (node (ref "JP_SWD") (pin "4") (pinfunction "4_4") (pintype "passive"))
      (node (ref "K1") (pin "2") (pinfunction "2_2") (pintype "passive"))
      (node (ref "K1") (pin "4") (pinfunction "4_4") (pintype "passive"))
      (node (ref "K2") (pin "2") (pinfunction "2_2") (pintype "passive"))
      (node (ref "K2") (pin "4") (pinfunction "4_4") (pintype "passive"))
      (node (ref "K3") (pin "2") (pinfunction "2_2") (pintype "passive"))
      (node (ref "K3") (pin "4") (pinfunction "4_4") (pintype "passive"))
      (node (ref "LED_PW") (pin "2") (pinfunction "K_2") (pintype "passive"))
      (node (ref "MP2236") (pin "4") (pinfunction "GND_4") (pintype "power_in"))
      (node (ref "R11") (pin "1") (pinfunction "1_1") (pintype "passive"))
      (node (ref "R12") (pin "2") (pinfunction "2_2") (pintype "passive"))
      (node (ref "R19") (pin "1") (pinfunction "1_1") (pintype "passive"))
      (node (ref "R25") (pin "1") (pinfunction "1_1") (pintype "passive"))
      (node (ref "R26") (pin "1") (pinfunction "1_1") (pintype "passive"))
      (node (ref "R5") (pin "1") (pinfunction "1_1") (pintype "passive"))
      (node (ref "R6") (pin "2") (pinfunction "2_2") (pintype "passive"))
      (node (ref "R9") (pin "2") (pinfunction "2_2") (pintype "passive"))
      (node (ref "U1") (pin "29") (pinfunction "HEAT_TAB_29") (pintype "passive"))
      (node (ref "U1") (pin "3") (pinfunction "GND_3") (pintype "passive"))
      (node (ref "U2") (pin "12") (pinfunction "VSSA_12") (pintype "power_in"))
      (node (ref "U2") (pin "18") (pinfunction "VSS_4_18") (pintype "power_in"))
      (node (ref "U2") (pin "31") (pinfunction "VSS_1_31") (pintype "power_in"))
      (node (ref "U2") (pin "47") (pinfunction "VSS_2_47") (pintype "power_in"))
      (node (ref "U2") (pin "63") (pinfunction "VSS_3_63") (pintype "power_in"))
      (node (ref "U3") (pin "1") (pinfunction "CLKIN_1") (pintype "passive"))
      (node (ref "U3") (pin "11") (pinfunction "FSYNC_11") (pintype "passive"))
      (node (ref "U3") (pin "18") (pinfunction "GND_18") (pintype "passive"))
      (node (ref "U4") (pin "10") (pinfunction "PGND2_10") (pintype "passive"))
      (node (ref "U4") (pin "18") (pinfunction "GND_18") (pintype "passive"))
      (node (ref "U4") (pin "3") (pinfunction "PGND1_3") (pintype "passive"))
      (node (ref "U4") (pin "4") (pinfunction "PGND1_4") (pintype "passive"))
      (node (ref "U4") (pin "9") (pinfunction "PGND2_9") (pintype "passive"))
      (node (ref "U5") (pin "10") (pinfunction "PGND2_10") (pintype "passive"))
      (node (ref "U5") (pin "18") (pinfunction "GND_18") (pintype "passive"))
      (node (ref "U5") (pin "3") (pinfunction "PGND1_3") (pintype "passive"))
      (node (ref "U5") (pin "4") (pinfunction "PGND1_4") (pintype "passive"))
      (node (ref "U5") (pin "9") (pinfunction "PGND2_9") (pintype "passive"))
      (node (ref "USB1") (pin "1") (pinfunction "SH1_1") (pintype "passive"))
      (node (ref "USB1") (pin "2") (pinfunction "SH2_2") (pintype "passive"))
      (node (ref "USB1") (pin "3") (pinfunction "SH3_3") (pintype "passive"))
      (node (ref "USB1") (pin "4") (pinfunction "SH4_4") (pintype "passive"))
      (node (ref "USB1") (pin "A1") (pinfunction "GND_A1") (pintype "passive"))
      (node (ref "USB1") (pin "A12") (pinfunction "GND_A12") (pintype "passive"))
      (node (ref "USB1") (pin "B1") (pinfunction "GND_B1") (pintype "passive"))
      (node (ref "USB1") (pin "B12") (pinfunction "GND_B12") (pintype "passive"))
      (node (ref "VIN1") (pin "2") (pinfunction "2_2") (pintype "passive"))
      (node (ref "X1") (pin "2") (pinfunction "2_2") (pintype "passive"))
      (node (ref "X1") (pin "4") (pinfunction "4_4") (pintype "passive"))
    )
    (net (code "67") (name "Net-(C5-Pad2)") (class "Default")
      (node (ref "C5") (pin "2") (pinfunction "2_2") (pintype "passive"))
      (node (ref "R2") (pin "2") (pinfunction "2_2") (pintype "passive"))
    )
    (net (code "68") (name "Net-(C9-Pad2)") (class "Default")
      (node (ref "C9") (pin "2") (pinfunction "2_2") (pintype "passive"))
      (node (ref "R3") (pin "2") (pinfunction "2_2") (pintype "passive"))
      (node (ref "R4") (pin "1") (pinfunction "1_1") (pintype "passive"))
      (node (ref "R5") (pin "2") (pinfunction "2_2") (pintype "passive"))
    )
    (net (code "69") (name "Net-(D2-K)") (class "Default")
      (node (ref "D2") (pin "2") (pinfunction "K_2") (pintype "passive"))
      (node (ref "Q1") (pin "3") (pinfunction "C_3") (pintype "passive"))
      (node (ref "R21") (pin "2") (pinfunction "2_2") (pintype "passive"))
    )
    (net (code "70") (name "Net-(D4-A)") (class "Default")
      (node (ref "D4") (pin "1") (pinfunction "A_1") (pintype "passive"))
      (node (ref "F1") (pin "2") (pinfunction "2_2") (pintype "passive"))
    )
    (net (code "71") (name "Net-(LED_BLUE-A)") (class "Default")
      (node (ref "LED_BLUE") (pin "1") (pinfunction "A_1") (pintype "passive"))
      (node (ref "R16") (pin "1") (pinfunction "1_1") (pintype "passive"))
    )
    (net (code "72") (name "Net-(LED_GREEN-A)") (class "Default")
      (node (ref "LED_GREEN") (pin "1") (pinfunction "A_1") (pintype "passive"))
      (node (ref "R15") (pin "1") (pinfunction "1_1") (pintype "passive"))
    )
    (net (code "73") (name "Net-(LED_PW-A)") (class "Default")
      (node (ref "LED_PW") (pin "1") (pinfunction "A_1") (pintype "passive"))
      (node (ref "R17") (pin "1") (pinfunction "1_1") (pintype "passive"))
    )
    (net (code "74") (name "Net-(MP2236-AGND)") (class "Default")
      (node (ref "MP2236") (pin "1") (pinfunction "AGND_1") (pintype "power_in"))
      (node (ref "R6") (pin "1") (pinfunction "1_1") (pintype "passive"))
      (node (ref "R7") (pin "1") (pinfunction "1_1") (pintype "passive"))
    )
    (net (code "75") (name "Net-(MP2236-BST)") (class "Default")
      (node (ref "MP2236") (pin "5") (pinfunction "BST_5") (pintype "power_in"))
      (node (ref "R2") (pin "1") (pinfunction "1_1") (pintype "passive"))
    )
    (net (code "76") (name "Net-(MP2236-EN{slash}SYNC)") (class "Default")
      (node (ref "MP2236") (pin "6") (pinfunction "EN/SYNC_6") (pintype "passive"))
      (node (ref "R1") (pin "2") (pinfunction "2_2") (pintype "passive"))
    )
    (net (code "77") (name "Net-(MP2236-FB)") (class "Default")
      (node (ref "MP2236") (pin "8") (pinfunction "FB_8") (pintype "passive"))
      (node (ref "R3") (pin "1") (pinfunction "1_1") (pintype "passive"))
    )
    (net (code "78") (name "Net-(MP2236-SW)") (class "Default")
      (node (ref "C5") (pin "1") (pinfunction "1_1") (pintype "passive"))
      (node (ref "L1") (pin "1") (pinfunction "1_1") (pintype "passive"))
      (node (ref "MP2236") (pin "3") (pinfunction "SW_3") (pintype "output"))
    )
    (net (code "79") (name "Net-(MP2236-VCC)") (class "Default")
      (node (ref "C4") (pin "1") (pinfunction "1_1") (pintype "passive"))
      (node (ref "MP2236") (pin "7") (pinfunction "VCC_7") (pintype "power_in"))
      (node (ref "R7") (pin "2") (pinfunction "2_2") (pintype "passive"))
    )
    (net (code "80") (name "Net-(Q1-B)") (class "Default")
      (node (ref "Q1") (pin "1") (pinfunction "B_1") (pintype "passive"))
      (node (ref "R22") (pin "2") (pinfunction "2_2") (pintype "passive"))
    )
    (net (code "81") (name "Net-(Q2-B)") (class "Default")
      (node (ref "Q2") (pin "1") (pinfunction "B_1") (pintype "passive"))
      (node (ref "R23") (pin "2") (pinfunction "2_2") (pintype "passive"))
    )
    (net (code "82") (name "Net-(Q2-C)") (class "Default")
      (node (ref "Q2") (pin "3") (pinfunction "C_3") (pintype "passive"))
      (node (ref "R24") (pin "1") (pinfunction "1_1") (pintype "passive"))
    )
    (net (code "83") (name "Net-(S1-Pad1)") (class "Default")
      (node (ref "S1") (pin "1") (pinfunction "1_1") (pintype "passive"))
      (node (ref "VIN1") (pin "1") (pinfunction "1_1") (pintype "passive"))
    )
    (net (code "84") (name "Net-(U1-*RST)") (class "Default")
      (node (ref "R20") (pin "1") (pinfunction "1_1") (pintype "passive"))
      (node (ref "U1") (pin "9") (pinfunction "*RST_9") (pintype "passive"))
    )
    (net (code "85") (name "Net-(U3-AD0)") (class "Default")
      (node (ref "R11") (pin "2") (pinfunction "2_2") (pintype "passive"))
      (node (ref "U3") (pin "9") (pinfunction "AD0_9") (pintype "passive"))
    )
    (net (code "86") (name "Net-(U3-CPOUT)") (class "Default")
      (node (ref "C33") (pin "1") (pinfunction "1_1") (pintype "passive"))
      (node (ref "U3") (pin "20") (pinfunction "CPOUT_20") (pintype "passive"))
    )
    (net (code "87") (name "Net-(U3-REGOUT)") (class "Default")
      (node (ref "C32") (pin "2") (pinfunction "2_2") (pintype "passive"))
      (node (ref "U3") (pin "10") (pinfunction "REGOUT_10") (pintype "passive"))
    )
    (net (code "88") (name "Net-(USB1-CC1)") (class "Default")
      (node (ref "R25") (pin "2") (pinfunction "2_2") (pintype "passive"))
      (node (ref "USB1") (pin "A5") (pinfunction "CC1_A5") (pintype "passive"))
    )
    (net (code "89") (name "Net-(USB1-CC2)") (class "Default")
      (node (ref "R26") (pin "2") (pinfunction "2_2") (pintype "passive"))
      (node (ref "USB1") (pin "B5") (pinfunction "CC2_B5") (pintype "passive"))
    )
    (net (code "90") (name "USB_5V") (class "Default")
      (node (ref "AMS1") (pin "3") (pinfunction "Vin_3") (pintype "passive"))
      (node (ref "C27") (pin "2") (pinfunction "2_2") (pintype "passive"))
      (node (ref "C28") (pin "2") (pinfunction "2_2") (pintype "passive"))
      (node (ref "D3") (pin "2") (pinfunction "K_2") (pintype "passive"))
      (node (ref "D4") (pin "2") (pinfunction "K_2") (pintype "passive"))
    )
    (net (code "91") (name "USB_5VIN") (class "Default")
      (node (ref "F1") (pin "1") (pinfunction "1_1") (pintype "passive"))
      (node (ref "R20") (pin "2") (pinfunction "2_2") (pintype "passive"))
      (node (ref "U1") (pin "7") (pinfunction "REGIN_7") (pintype "passive"))
      (node (ref "U1") (pin "8") (pinfunction "VBUS_8") (pintype "passive"))
      (node (ref "USB1") (pin "A4") (pinfunction "VBUS_A4") (pintype "passive"))
      (node (ref "USB1") (pin "A9") (pinfunction "VBUS_A9") (pintype "passive"))
      (node (ref "USB1") (pin "B4") (pinfunction "VBUS_B4") (pintype "passive"))
      (node (ref "USB1") (pin "B9") (pinfunction "VBUS_B9") (pintype "passive"))
    )
    (net (code "92") (name "VCC3V3") (class "Default")
      (node (ref "AMS1") (pin "2") (pinfunction "Vout_2") (pintype "passive"))
      (node (ref "AMS1") (pin "4") (pinfunction "Vout_4") (pintype "passive"))
      (node (ref "C21") (pin "2") (pinfunction "2_2") (pintype "passive"))
      (node (ref "C22") (pin "2") (pinfunction "2_2") (pintype "passive"))
      (node (ref "C23") (pin "2") (pinfunction "2_2") (pintype "passive"))
      (node (ref "C24") (pin "2") (pinfunction "2_2") (pintype "passive"))
      (node (ref "C25") (pin "2") (pinfunction "2_2") (pintype "passive"))
      (node (ref "C26") (pin "2") (pinfunction "2_2") (pintype "passive"))
      (node (ref "C29") (pin "2") (pinfunction "2_2") (pintype "passive"))
      (node (ref "C30") (pin "2") (pinfunction "2_2") (pintype "passive"))
      (node (ref "C31") (pin "2") (pinfunction "2_2") (pintype "passive"))
      (node (ref "C34") (pin "1") (pinfunction "1_1") (pintype "passive"))
      (node (ref "JP1") (pin "1") (pinfunction "1_1") (pintype "passive"))
      (node (ref "JP1") (pin "2") (pinfunction "2_2") (pintype "passive"))
      (node (ref "JP1") (pin "3") (pinfunction "3_3") (pintype "passive"))
      (node (ref "JP1") (pin "4") (pinfunction "4_4") (pintype "passive"))
      (node (ref "JP1") (pin "5") (pinfunction "5_5") (pintype "passive"))
      (node (ref "JP1") (pin "6") (pinfunction "6_6") (pintype "passive"))
      (node (ref "JP1") (pin "7") (pinfunction "7_7") (pintype "passive"))
      (node (ref "JP_SWD") (pin "1") (pinfunction "1_1") (pintype "passive"))
      (node (ref "Q2") (pin "2") (pinfunction "E_2") (pintype "passive"))
      (node (ref "R10") (pin "2") (pinfunction "2_2") (pintype "passive"))
      (node (ref "R14") (pin "2") (pinfunction "2_2") (pintype "passive"))
      (node (ref "R15") (pin "2") (pinfunction "2_2") (pintype "passive"))
      (node (ref "R16") (pin "2") (pinfunction "2_2") (pintype "passive"))
      (node (ref "R17") (pin "2") (pinfunction "2_2") (pintype "passive"))
      (node (ref "R21") (pin "1") (pinfunction "1_1") (pintype "passive"))
      (node (ref "R8") (pin "2") (pinfunction "2_2") (pintype "passive"))
      (node (ref "U2") (pin "1") (pinfunction "VBAT_1") (pintype "power_in"))
      (node (ref "U2") (pin "13") (pinfunction "VDDA_13") (pintype "power_in"))
      (node (ref "U2") (pin "19") (pinfunction "VDD_4_19") (pintype "power_in"))
      (node (ref "U2") (pin "32") (pinfunction "VDD_1_32") (pintype "power_in"))
      (node (ref "U2") (pin "48") (pinfunction "VDD_2_48") (pintype "power_in"))
      (node (ref "U2") (pin "64") (pinfunction "VDD_3_64") (pintype "power_in"))
      (node (ref "U3") (pin "13") (pinfunction "VDD_13") (pintype "passive"))
      (node (ref "U3") (pin "8") (pinfunction "VLogic_8") (pintype "passive"))
    )
    (net (code "93") (name "VCC5V") (class "Default")
      (node (ref "C17") (pin "1") (pinfunction "1_1") (pintype "passive"))
      (node (ref "C18") (pin "2") (pinfunction "2_2") (pintype "passive"))
      (node (ref "C19") (pin "1") (pinfunction "1_1") (pintype "passive"))
      (node (ref "C20") (pin "2") (pinfunction "2_2") (pintype "passive"))
      (node (ref "C6") (pin "2") (pinfunction "2_2") (pintype "passive"))
      (node (ref "C7") (pin "2") (pinfunction "2_2") (pintype "passive"))
      (node (ref "C8") (pin "2") (pinfunction "2_2") (pintype "passive"))
      (node (ref "C9") (pin "1") (pinfunction "1_1") (pintype "passive"))
      (node (ref "D3") (pin "1") (pinfunction "A_1") (pintype "passive"))
      (node (ref "EM1") (pin "2") (pinfunction "2_2") (pintype "passive"))
      (node (ref "EM2") (pin "2") (pinfunction "2_2") (pintype "passive"))
      (node (ref "EM3") (pin "2") (pinfunction "2_2") (pintype "passive"))
      (node (ref "EM4") (pin "2") (pinfunction "2_2") (pintype "passive"))
      (node (ref "JP2") (pin "1") (pinfunction "1_1") (pintype "passive"))
      (node (ref "JP2") (pin "2") (pinfunction "2_2") (pintype "passive"))
      (node (ref "JP2") (pin "3") (pinfunction "3_3") (pintype "passive"))
      (node (ref "JP2") (pin "4") (pinfunction "4_4") (pintype "passive"))
      (node (ref "JP2") (pin "5") (pinfunction "5_5") (pintype "passive"))
      (node (ref "JP2") (pin "6") (pinfunction "6_6") (pintype "passive"))
      (node (ref "JP2") (pin "7") (pinfunction "7_7") (pintype "passive"))
      (node (ref "JP_PI") (pin "1") (pinfunction "1_1") (pintype "passive"))
      (node (ref "L1") (pin "2") (pinfunction "2_2") (pintype "passive"))
      (node (ref "R4") (pin "2") (pinfunction "2_2") (pintype "passive"))
      (node (ref "RP12") (pin "5") (pinfunction "5_5") (pintype "passive"))
      (node (ref "RP12") (pin "6") (pinfunction "6_6") (pintype "passive"))
      (node (ref "RP12") (pin "7") (pinfunction "7_7") (pintype "passive"))
      (node (ref "RP12") (pin "8") (pinfunction "8_8") (pintype "passive"))
      (node (ref "RP34") (pin "5") (pinfunction "5_5") (pintype "passive"))
      (node (ref "RP34") (pin "6") (pinfunction "6_6") (pintype "passive"))
      (node (ref "RP34") (pin "7") (pinfunction "7_7") (pintype "passive"))
      (node (ref "RP34") (pin "8") (pinfunction "8_8") (pintype "passive"))
      (node (ref "U4") (pin "19") (pinfunction "STBY_19") (pintype "passive"))
      (node (ref "U4") (pin "20") (pinfunction "VCC_20") (pintype "passive"))
      (node (ref "U5") (pin "19") (pinfunction "STBY_19") (pintype "passive"))
      (node (ref "U5") (pin "20") (pinfunction "VCC_20") (pintype "passive"))
    )
    (net (code "94") (name "VCC12V") (class "Default")
      (node (ref "C1") (pin "2") (pinfunction "2_2") (pintype "passive"))
      (node (ref "C13") (pin "2") (pinfunction "2_2") (pintype "passive"))
      (node (ref "C14") (pin "2") (pinfunction "2_2") (pintype "passive"))
      (node (ref "C15") (pin "2") (pinfunction "2_2") (pintype "passive"))
      (node (ref "C16") (pin "2") (pinfunction "2_2") (pintype "passive"))
      (node (ref "C2") (pin "2") (pinfunction "2_2") (pintype "passive"))
      (node (ref "C3") (pin "2") (pinfunction "2_2") (pintype "passive"))
      (node (ref "D1") (pin "2") (pinfunction "K_2") (pintype "passive"))
      (node (ref "MP2236") (pin "2") (pinfunction "IN_2") (pintype "power_in"))
      (node (ref "R1") (pin "1") (pinfunction "1_1") (pintype "passive"))
      (node (ref "R18") (pin "2") (pinfunction "2_2") (pintype "passive"))
      (node (ref "S1") (pin "2") (pinfunction "2_2") (pintype "passive"))
      (node (ref "U4") (pin "13") (pinfunction "VM2_13") (pintype "passive"))
      (node (ref "U4") (pin "14") (pinfunction "VM3_14") (pintype "passive"))
      (node (ref "U4") (pin "24") (pinfunction "VM1_24") (pintype "passive"))
      (node (ref "U5") (pin "13") (pinfunction "VM2_13") (pintype "passive"))
      (node (ref "U5") (pin "14") (pinfunction "VM3_14") (pintype "passive"))
      (node (ref "U5") (pin "24") (pinfunction "VM1_24") (pintype "passive"))
    )
    (net (code "95") (name "unconnected-(S1-Pad3)") (class "Default")
      (node (ref "S1") (pin "3") (pinfunction "3_3") (pintype "passive"))
    )
    (net (code "96") (name "unconnected-(U1-*SUSPEND-Pad11)") (class "Default")
      (node (ref "U1") (pin "11") (pinfunction "*SUSPEND_11") (pintype "passive"))
    )
    (net (code "97") (name "unconnected-(U1-CTS-Pad23)") (class "Default")
      (node (ref "U1") (pin "23") (pinfunction "CTS_23") (pintype "passive"))
    )
    (net (code "98") (name "unconnected-(U1-DCD-Pad1)") (class "Default")
      (node (ref "U1") (pin "1") (pinfunction "DCD_1") (pintype "passive"))
    )
    (net (code "99") (name "unconnected-(U1-DSR-Pad27)") (class "Default")
      (node (ref "U1") (pin "27") (pinfunction "DSR_27") (pintype "passive"))
    )
    (net (code "100") (name "unconnected-(U1-NC-Pad10)") (class "Default")
      (node (ref "U1") (pin "10") (pinfunction "NC_10") (pintype "passive"))
    )
    (net (code "101") (name "unconnected-(U1-NC-Pad13)") (class "Default")
      (node (ref "U1") (pin "13") (pinfunction "NC_13") (pintype "passive"))
    )
    (net (code "102") (name "unconnected-(U1-NC-Pad14)") (class "Default")
      (node (ref "U1") (pin "14") (pinfunction "NC_14") (pintype "passive"))
    )
    (net (code "103") (name "unconnected-(U1-NC-Pad15)") (class "Default")
      (node (ref "U1") (pin "15") (pinfunction "NC_15") (pintype "passive"))
    )
    (net (code "104") (name "unconnected-(U1-NC-Pad16)") (class "Default")
      (node (ref "U1") (pin "16") (pinfunction "NC_16") (pintype "passive"))
    )
    (net (code "105") (name "unconnected-(U1-NC-Pad17)") (class "Default")
      (node (ref "U1") (pin "17") (pinfunction "NC_17") (pintype "passive"))
    )
    (net (code "106") (name "unconnected-(U1-NC-Pad18)") (class "Default")
      (node (ref "U1") (pin "18") (pinfunction "NC_18") (pintype "passive"))
    )
    (net (code "107") (name "unconnected-(U1-NC-Pad19)") (class "Default")
      (node (ref "U1") (pin "19") (pinfunction "NC_19") (pintype "passive"))
    )
    (net (code "108") (name "unconnected-(U1-NC-Pad20)") (class "Default")
      (node (ref "U1") (pin "20") (pinfunction "NC_20") (pintype "passive"))
    )
    (net (code "109") (name "unconnected-(U1-NC-Pad21)") (class "Default")
      (node (ref "U1") (pin "21") (pinfunction "NC_21") (pintype "passive"))
    )
    (net (code "110") (name "unconnected-(U1-NC-Pad22)") (class "Default")
      (node (ref "U1") (pin "22") (pinfunction "NC_22") (pintype "passive"))
    )
    (net (code "111") (name "unconnected-(U1-RI-Pad2)") (class "Default")
      (node (ref "U1") (pin "2") (pinfunction "RI_2") (pintype "passive"))
    )
    (net (code "112") (name "unconnected-(U1-SUSPEND-Pad12)") (class "Default")
      (node (ref "U1") (pin "12") (pinfunction "SUSPEND_12") (pintype "passive"))
    )
    (net (code "113") (name "unconnected-(U1-VDD-Pad6)") (class "Default")
      (node (ref "U1") (pin "6") (pinfunction "VDD_6") (pintype "passive"))
    )
    (net (code "114") (name "unconnected-(U3-A_CL-Pad7)") (class "Default")
      (node (ref "U3") (pin "7") (pinfunction "A_CL_7") (pintype "passive+no_connect"))
    )
    (net (code "115") (name "unconnected-(U3-A_DA-Pad6)") (class "Default")
      (node (ref "U3") (pin "6") (pinfunction "A_DA_6") (pintype "passive+no_connect"))
    )
    (net (code "116") (name "unconnected-(U3-CLKOUT-Pad22)") (class "Default")
      (node (ref "U3") (pin "22") (pinfunction "CLKOUT_22") (pintype "passive+no_connect"))
    )
    (net (code "117") (name "unconnected-(U3-NC-Pad2)") (class "Default")
      (node (ref "U3") (pin "2") (pinfunction "NC_2") (pintype "passive+no_connect"))
    )
    (net (code "118") (name "unconnected-(U3-NC-Pad3)") (class "Default")
      (node (ref "U3") (pin "3") (pinfunction "NC_3") (pintype "passive+no_connect"))
    )
    (net (code "119") (name "unconnected-(U3-NC-Pad4)") (class "Default")
      (node (ref "U3") (pin "4") (pinfunction "NC_4") (pintype "passive+no_connect"))
    )
    (net (code "120") (name "unconnected-(U3-NC-Pad5)") (class "Default")
      (node (ref "U3") (pin "5") (pinfunction "NC_5") (pintype "passive+no_connect"))
    )
    (net (code "121") (name "unconnected-(U3-NC-Pad14)") (class "Default")
      (node (ref "U3") (pin "14") (pinfunction "NC_14") (pintype "passive"))
    )
    (net (code "122") (name "unconnected-(U3-NC-Pad15)") (class "Default")
      (node (ref "U3") (pin "15") (pinfunction "NC_15") (pintype "passive"))
    )
    (net (code "123") (name "unconnected-(U3-NC-Pad16)") (class "Default")
      (node (ref "U3") (pin "16") (pinfunction "NC_16") (pintype "passive"))
    )
    (net (code "124") (name "unconnected-(U3-NC-Pad17)") (class "Default")
      (node (ref "U3") (pin "17") (pinfunction "NC_17") (pintype "passive"))
    )
    (net (code "125") (name "unconnected-(U3-RESV-Pad19)") (class "Default")
      (node (ref "U3") (pin "19") (pinfunction "RESV_19") (pintype "passive+no_connect"))
    )
    (net (code "126") (name "unconnected-(U3-RESV-Pad21)") (class "Default")
      (node (ref "U3") (pin "21") (pinfunction "RESV_21") (pintype "passive+no_connect"))
    )
    (net (code "127") (name "unconnected-(USB1-RX1+-PadB11)") (class "Default")
      (node (ref "USB1") (pin "B11") (pinfunction "RX1+_B11") (pintype "passive"))
    )
    (net (code "128") (name "unconnected-(USB1-RX1--PadB10)") (class "Default")
      (node (ref "USB1") (pin "B10") (pinfunction "RX1-_B10") (pintype "passive"))
    )
    (net (code "129") (name "unconnected-(USB1-RX2+-PadA11)") (class "Default")
      (node (ref "USB1") (pin "A11") (pinfunction "RX2+_A11") (pintype "passive"))
    )
    (net (code "130") (name "unconnected-(USB1-RX2--PadA10)") (class "Default")
      (node (ref "USB1") (pin "A10") (pinfunction "RX2-_A10") (pintype "passive"))
    )
    (net (code "131") (name "unconnected-(USB1-SBU1-PadA8)") (class "Default")
      (node (ref "USB1") (pin "A8") (pinfunction "SBU1_A8") (pintype "passive"))
    )
    (net (code "132") (name "unconnected-(USB1-SBU2-PadB8)") (class "Default")
      (node (ref "USB1") (pin "B8") (pinfunction "SBU2_B8") (pintype "passive"))
    )
    (net (code "133") (name "unconnected-(USB1-TX1+-PadA2)") (class "Default")
      (node (ref "USB1") (pin "A2") (pinfunction "TX1+_A2") (pintype "passive"))
    )
    (net (code "134") (name "unconnected-(USB1-TX1--PadA3)") (class "Default")
      (node (ref "USB1") (pin "A3") (pinfunction "TX1-_A3") (pintype "passive"))
    )
    (net (code "135") (name "unconnected-(USB1-TX2+-PadB2)") (class "Default")
      (node (ref "USB1") (pin "B2") (pinfunction "TX2+_B2") (pintype "passive"))
    )
    (net (code "136") (name "unconnected-(USB1-TX2--PadB3)") (class "Default")
      (node (ref "USB1") (pin "B3") (pinfunction "TX2-_B3") (pintype "passive"))
    )
  )
)
